# RS485_SN75176B.net
KiCad netlist of a schematic drawn in Altium Designer
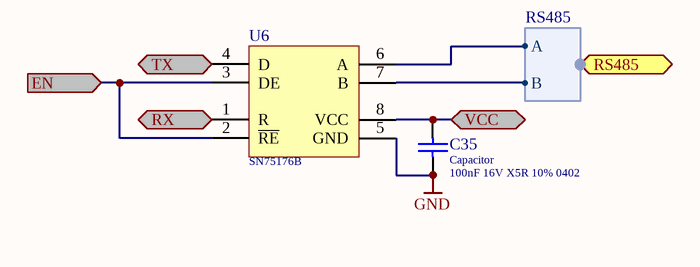
[diagram p0: RS485_SN75176B.SchDoc]

(export (version "E")
  (design (tool "Eeschema 10.0.6"))
  (components
    (comp (ref "C35")
      (value "Capacitor")
      (footprint "CAP_SMD:0402")
      (description "Ceramic capacitor")
      (fields
        (field (name "VOLTAGE") "16V")
        (field (name "TOLERANCE") "10%")
        (field (name "ALTIUM_VALUE") "100nF 16V X5R 10% ")
      )
      (libsource (lib "Passive") (part "Capacitor ceramic"))
    )
    (comp (ref "U6")
      (value "SN75176B")
      (footprint "SOIC:SOIC-8")
      (description "3.3 V, 15 kV ESD, 12 Mbps RS-485/RS-422 transceiver")
      (libsource (lib "IC_RSxxx") (part "SN75176B"))
    )
  )
  (nets
    (net (code "2") (name "/A") (class "Default")
      (node (ref "U6") (pin "6") (pinfunction "A_6") (pintype "passive"))
    )
    (net (code "3") (name "/B") (class "Default")
      (node (ref "U6") (pin "7") (pinfunction "B_7") (pintype "passive"))
    )
    (net (code "4") (name "/EN") (class "Default")
      (node (ref "U6") (pin "2") (pinfunction "~{RE}_2") (pintype "passive"))
      (node (ref "U6") (pin "3") (pinfunction "DE_3") (pintype "passive"))
    )
    (net (code "5") (name "/RX") (class "Default")
      (node (ref "U6") (pin "1") (pinfunction "R_1") (pintype "passive"))
    )
    (net (code "6") (name "/TX") (class "Default")
      (node (ref "U6") (pin "4") (pinfunction "D_4") (pintype "passive"))
    )
    (net (code "7") (name "/VCC") (class "Default")
      (node (ref "C35") (pin "2") (pinfunction "2_2") (pintype "passive"))
      (node (ref "U6") (pin "8") (pinfunction "VCC_8") (pintype "passive"))
    )
    (net (code "9") (name "GND") (class "Default")
      (node (ref "C35") (pin "1") (pinfunction "1_1") (pintype "passive"))
      (node (ref "U6") (pin "5") (pinfunction "GND_5") (pintype "passive"))
    )
  )
)
